# LMH6629_test.net
KiCad netlist of a schematic drawn in EAGLE
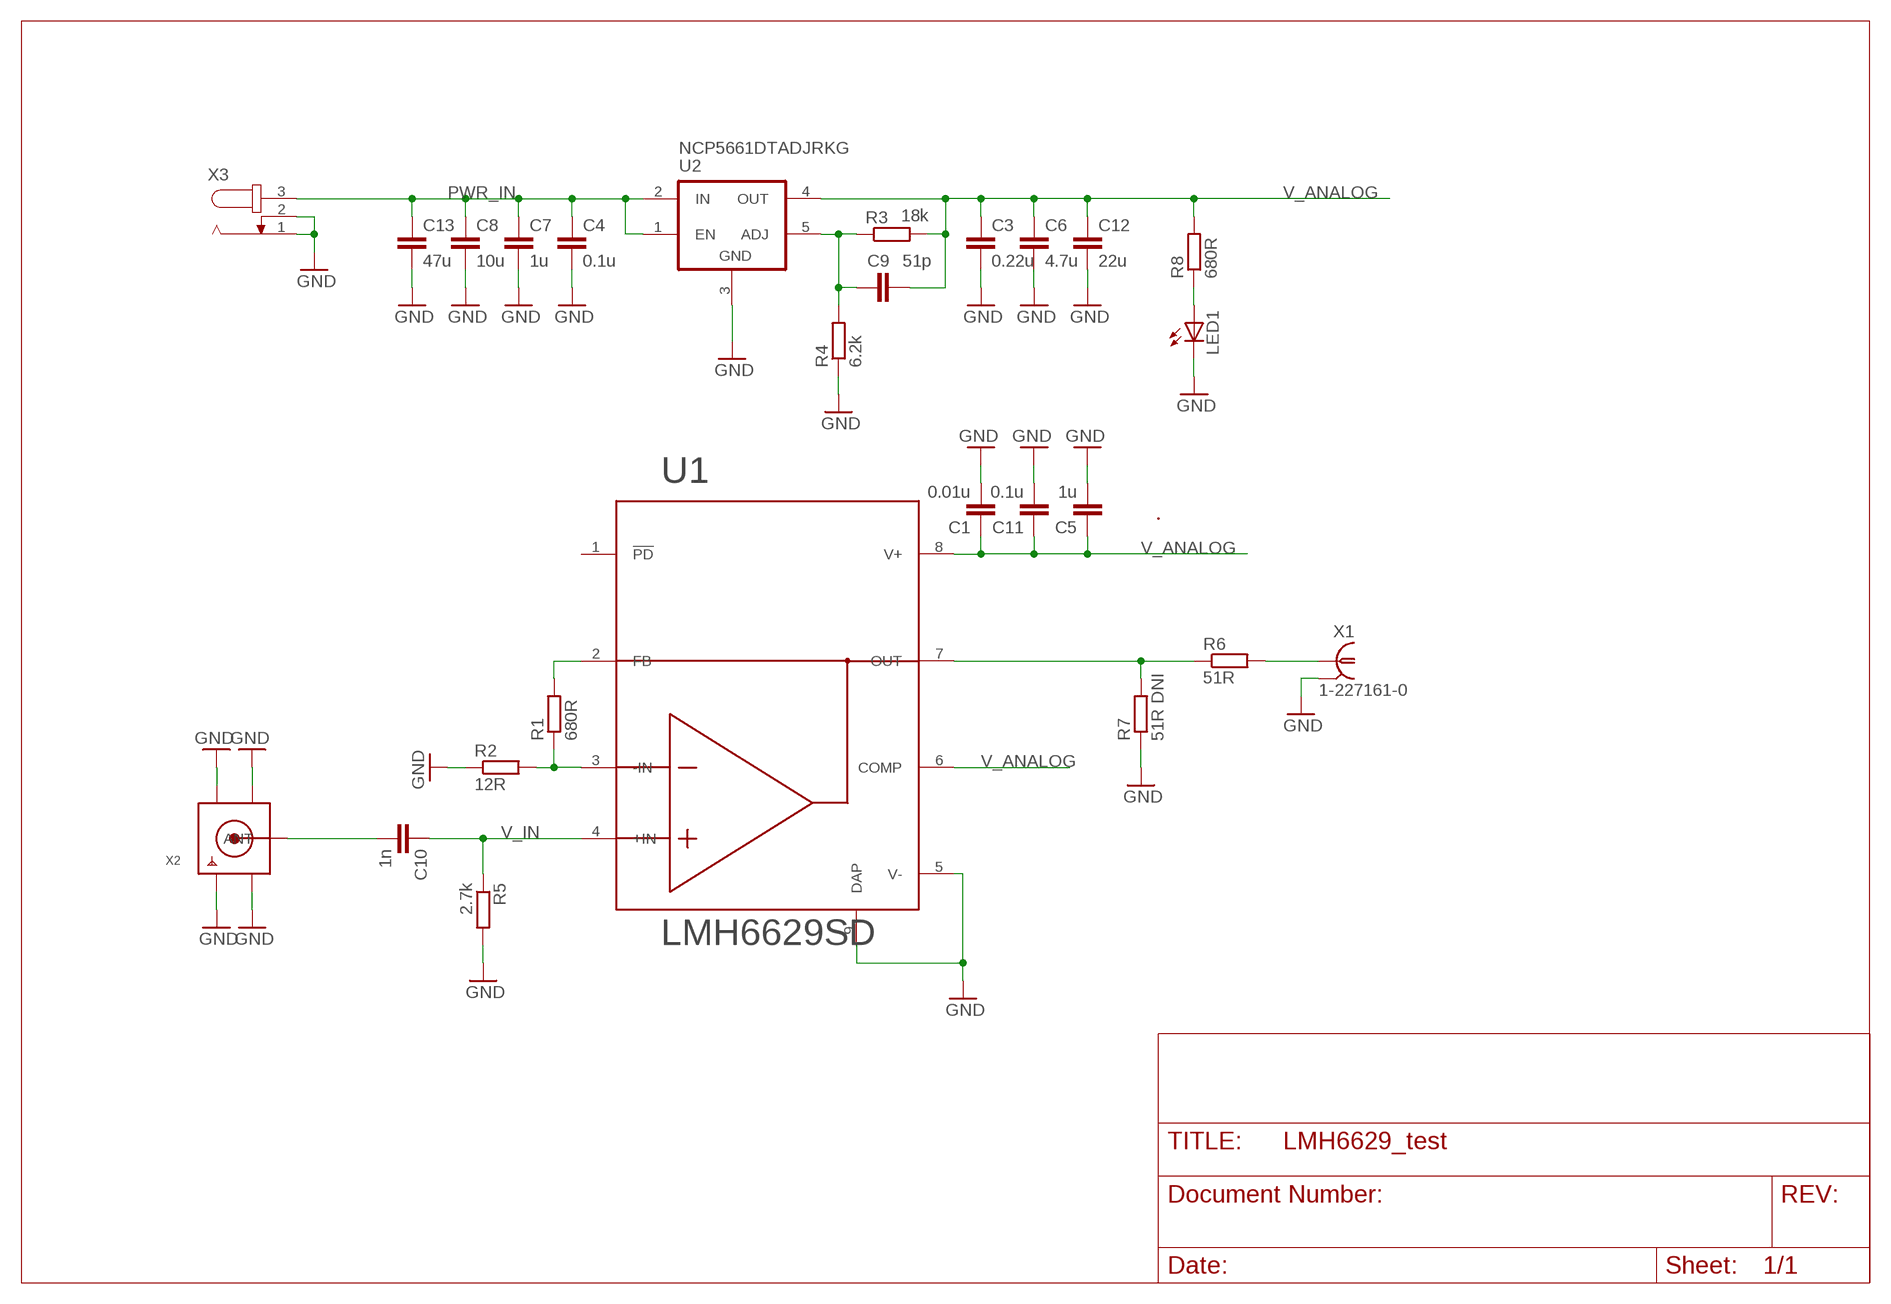
[diagram p0: schematic, sheet 1]

(export (version "E")
  (design (tool "Eeschema 10.0.6"))
  (components
    (comp (ref "C1")
      (value "0.01u")
      (footprint "eagle-import:C0603")
      (libsource (lib "eagle-import") (part "C-EUC0603"))
    )
    (comp (ref "C3")
      (value "0.22u")
      (footprint "eagle-import:C0603")
      (libsource (lib "eagle-import") (part "C-EUC0603"))
    )
    (comp (ref "C4")
      (value "0.1u")
      (footprint "eagle-import:C0603")
      (libsource (lib "eagle-import") (part "C-EUC0603"))
    )
    (comp (ref "C5")
      (value "1u")
      (footprint "eagle-import:C0603")
      (libsource (lib "eagle-import") (part "C-EUC0603"))
    )
    (comp (ref "C6")
      (value "4.7u")
      (footprint "eagle-import:C0805")
      (libsource (lib "eagle-import") (part "C-EUC0805"))
    )
    (comp (ref "C7")
      (value "1u")
      (footprint "eagle-import:C0603")
      (libsource (lib "eagle-import") (part "C-EUC0603"))
    )
    (comp (ref "C8")
      (value "10u")
      (footprint "eagle-import:C0805")
      (libsource (lib "eagle-import") (part "C-EUC0805"))
    )
    (comp (ref "C9")
      (value "51p")
      (footprint "eagle-import:C0603")
      (libsource (lib "eagle-import") (part "C-EUC0603"))
    )
    (comp (ref "C10")
      (value "1n")
      (footprint "eagle-import:C0603")
      (libsource (lib "eagle-import") (part "C-EUC0603"))
    )
    (comp (ref "C11")
      (value "0.1u")
      (footprint "eagle-import:C0603")
      (libsource (lib "eagle-import") (part "C-EUC0603"))
    )
    (comp (ref "C12")
      (value "22u")
      (footprint "eagle-import:C0805")
      (libsource (lib "eagle-import") (part "C-EUC0805"))
    )
    (comp (ref "C13")
      (value "47u")
      (footprint "eagle-import:C1210")
      (libsource (lib "eagle-import") (part "resistor_348_C-EUC1210"))
    )
    (comp (ref "LED1")
      (value "LEDCHIPLED_0603")
      (footprint "eagle-import:CHIPLED_0603")
      (libsource (lib "eagle-import") (part "LEDCHIPLED_0603"))
    )
    (comp (ref "R1")
      (value "680R")
      (footprint "eagle-import:R0402")
      (libsource (lib "eagle-import") (part "R-EU_R0402"))
    )
    (comp (ref "R2")
      (value "12R")
      (footprint "eagle-import:R0402")
      (libsource (lib "eagle-import") (part "R-EU_R0402"))
    )
    (comp (ref "R3")
      (value "18k")
      (footprint "eagle-import:R0603")
      (libsource (lib "eagle-import") (part "R-EU_R0603"))
    )
    (comp (ref "R4")
      (value "6.2k")
      (footprint "eagle-import:R0603")
      (libsource (lib "eagle-import") (part "R-EU_R0603"))
    )
    (comp (ref "R5")
      (value "2.7k")
      (footprint "eagle-import:R0603")
      (libsource (lib "eagle-import") (part "R-EU_R0603"))
    )
    (comp (ref "R6")
      (value "51R")
      (footprint "eagle-import:R0603")
      (libsource (lib "eagle-import") (part "R-EU_R0603"))
    )
    (comp (ref "R7")
      (value "51R DNI")
      (footprint "eagle-import:R0603")
      (libsource (lib "eagle-import") (part "R-EU_R0603"))
    )
    (comp (ref "R8")
      (value "680R")
      (footprint "eagle-import:R0603")
      (libsource (lib "eagle-import") (part "R-EU_R0603"))
    )
    (comp (ref "U1")
      (value "LMH6629SD")
      (footprint "eagle-import:SON50P300X300X100-9N")
      (libsource (lib "eagle-import") (part "LMH6629SD"))
    )
    (comp (ref "U2")
      (value "NCP5661DTADJRKG")
      (footprint "eagle-import:DPAK-5")
      (libsource (lib "eagle-import") (part "NCP5661DTADJRKG"))
    )
    (comp (ref "X1")
      (value "1-227161-0")
      (footprint "eagle-import:AMP_227161")
      (fields (field (name "MF") "TYCO ELECTRONICS") (field (name "MPN") "1-227161"))
      (libsource (lib "eagle-import") (part "?2271611--0"))
    )
    (comp (ref "X2")
      (value "SMACONNECTOR_EDGE")
      (footprint "eagle-import:SMA_EDGELAUNCH")
      (libsource (lib "eagle-import") (part "SMACONNECTOR_EDGE"))
    )
    (comp (ref "X3")
      (value "JACK-PLUG1")
      (footprint "eagle-import:SPC4078")
      (libsource (lib "eagle-import") (part "JACK-PLUG1"))
    )
  )
  (nets
    (net (code "1") (name "/PWR_IN") (class "Default")
      (node (ref "C13") (pin "1") (pinfunction "1_1") (pintype "passive"))
      (node (ref "C4") (pin "1") (pinfunction "1_1") (pintype "passive"))
      (node (ref "C7") (pin "1") (pinfunction "1_1") (pintype "passive"))
      (node (ref "C8") (pin "1") (pinfunction "1_1") (pintype "passive"))
      (node (ref "U2") (pin "1") (pinfunction "EN_1") (pintype "input"))
      (node (ref "U2") (pin "2") (pinfunction "IN_2") (pintype "input"))
      (node (ref "X3") (pin "3") (pinfunction "3_3") (pintype "passive"))
    )
    (net (code "2") (name "/V_ANALOG") (class "Default")
      (node (ref "C1") (pin "1") (pinfunction "1_1") (pintype "passive"))
      (node (ref "C11") (pin "1") (pinfunction "1_1") (pintype "passive"))
      (node (ref "C12") (pin "1") (pinfunction "1_1") (pintype "passive"))
      (node (ref "C3") (pin "1") (pinfunction "1_1") (pintype "passive"))
      (node (ref "C5") (pin "1") (pinfunction "1_1") (pintype "passive"))
      (node (ref "C6") (pin "1") (pinfunction "1_1") (pintype "passive"))
      (node (ref "C9") (pin "2") (pinfunction "2_2") (pintype "passive"))
      (node (ref "R3") (pin "2") (pinfunction "2_2") (pintype "passive"))
      (node (ref "R8") (pin "2") (pinfunction "2_2") (pintype "passive"))
      (node (ref "U1") (pin "6") (pinfunction "COMP_6") (pintype "bidirectional"))
      (node (ref "U1") (pin "8") (pinfunction "V+_8") (pintype "bidirectional"))
      (node (ref "U2") (pin "4") (pinfunction "OUT_4") (pintype "output"))
    )
    (net (code "3") (name "/V_IN") (class "Default")
      (node (ref "C10") (pin "1") (pinfunction "1_1") (pintype "passive"))
      (node (ref "R5") (pin "1") (pinfunction "1_1") (pintype "passive"))
      (node (ref "U1") (pin "4") (pinfunction "+IN_4") (pintype "bidirectional"))
    )
    (net (code "4") (name "GND") (class "Default")
      (node (ref "C1") (pin "2") (pinfunction "2_2") (pintype "passive"))
      (node (ref "C11") (pin "2") (pinfunction "2_2") (pintype "passive"))
      (node (ref "C12") (pin "2") (pinfunction "2_2") (pintype "passive"))
      (node (ref "C13") (pin "2") (pinfunction "2_2") (pintype "passive"))
      (node (ref "C3") (pin "2") (pinfunction "2_2") (pintype "passive"))
      (node (ref "C4") (pin "2") (pinfunction "2_2") (pintype "passive"))
      (node (ref "C5") (pin "2") (pinfunction "2_2") (pintype "passive"))
      (node (ref "C6") (pin "2") (pinfunction "2_2") (pintype "passive"))
      (node (ref "C7") (pin "2") (pinfunction "2_2") (pintype "passive"))
      (node (ref "C8") (pin "2") (pinfunction "2_2") (pintype "passive"))
      (node (ref "LED1") (pin "C") (pinfunction "C_C") (pintype "passive"))
      (node (ref "R2") (pin "1") (pinfunction "1_1") (pintype "passive"))
      (node (ref "R4") (pin "1") (pinfunction "1_1") (pintype "passive"))
      (node (ref "R5") (pin "2") (pinfunction "2_2") (pintype "passive"))
      (node (ref "R7") (pin "1") (pinfunction "1_1") (pintype "passive"))
      (node (ref "U1") (pin "5") (pinfunction "V-_5") (pintype "bidirectional"))
      (node (ref "U1") (pin "9") (pinfunction "DAP_9") (pintype "bidirectional"))
      (node (ref "U2") (pin "3") (pinfunction "GND_3") (pintype "power_in"))
      (node (ref "X1") (pin "2") (pinfunction "2_2") (pintype "passive"))
      (node (ref "X2") (pin "GND@1") (pinfunction "GND4_GND@1") (pintype "power_in"))
      (node (ref "X2") (pin "GND@2") (pinfunction "GND3_GND@2") (pintype "power_in"))
      (node (ref "X2") (pin "GND@3") (pinfunction "GND2_GND@3") (pintype "power_in"))
      (node (ref "X2") (pin "GND@4") (pinfunction "GND1_GND@4") (pintype "power_in"))
      (node (ref "X3") (pin "1") (pinfunction "1_1") (pintype "passive"))
      (node (ref "X3") (pin "2") (pinfunction "2_2") (pintype "passive"))
    )
    (net (code "5") (name "Net-(LED1-PadA)") (class "Default")
      (node (ref "LED1") (pin "A") (pinfunction "A_A") (pintype "passive"))
      (node (ref "R8") (pin "1") (pinfunction "1_1") (pintype "passive"))
    )
    (net (code "6") (name "Net-(R6-Pad2)") (class "Default")
      (node (ref "R6") (pin "2") (pinfunction "2_2") (pintype "passive"))
      (node (ref "X1") (pin "1") (pinfunction "1_1") (pintype "passive"))
    )
    (net (code "7") (name "Net-(U1--IN)") (class "Default")
      (node (ref "R1") (pin "1") (pinfunction "1_1") (pintype "passive"))
      (node (ref "R2") (pin "2") (pinfunction "2_2") (pintype "passive"))
      (node (ref "U1") (pin "3") (pinfunction "-IN_3") (pintype "bidirectional"))
    )
    (net (code "8") (name "Net-(U1-FB)") (class "Default")
      (node (ref "R1") (pin "2") (pinfunction "2_2") (pintype "passive"))
      (node (ref "U1") (pin "2") (pinfunction "FB_2") (pintype "bidirectional"))
    )
    (net (code "9") (name "Net-(U1-OUT)") (class "Default")
      (node (ref "R6") (pin "1") (pinfunction "1_1") (pintype "passive"))
      (node (ref "R7") (pin "2") (pinfunction "2_2") (pintype "passive"))
      (node (ref "U1") (pin "7") (pinfunction "OUT_7") (pintype "bidirectional"))
    )
    (net (code "10") (name "Net-(U2-ADJ)") (class "Default")
      (node (ref "C9") (pin "1") (pinfunction "1_1") (pintype "passive"))
      (node (ref "R3") (pin "1") (pinfunction "1_1") (pintype "passive"))
      (node (ref "R4") (pin "2") (pinfunction "2_2") (pintype "passive"))
      (node (ref "U2") (pin "5") (pinfunction "ADJ_5") (pintype "input"))
    )
    (net (code "11") (name "Net-(X2-ANT)") (class "Default")
      (node (ref "C10") (pin "2") (pinfunction "2_2") (pintype "passive"))
      (node (ref "X2") (pin "P") (pinfunction "ANT_P") (pintype "bidirectional"))
    )
    (net (code "12") (name "unconnected-(U1-~{PD}-Pad1)") (class "Default")
      (node (ref "U1") (pin "1") (pinfunction "~{PD}_1") (pintype "bidirectional"))
    )
  )
)
